# CLK_DISTRO.net
KiCad netlist of a schematic drawn in Altium Designer
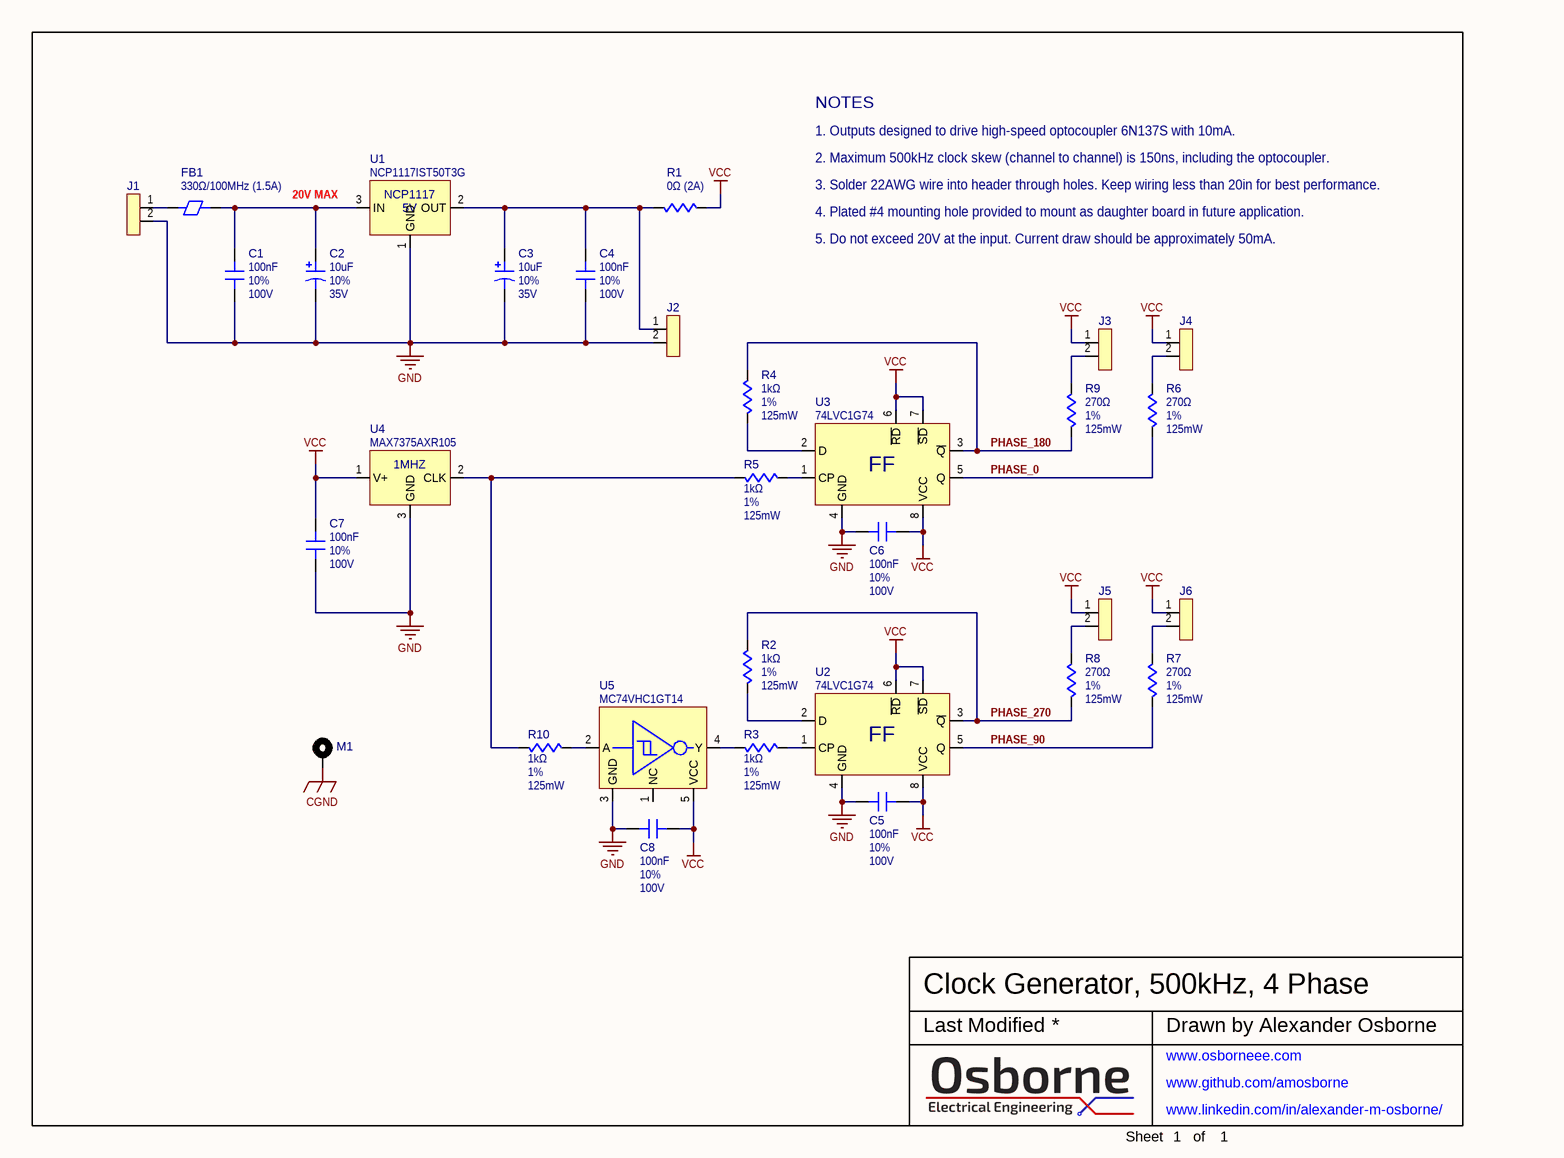
[diagram p0: CLK_DISTRO.SchDoc]

(export (version "E")
  (design (tool "Eeschema 10.0.6"))
  (components
    (comp (ref "C1")
      (value "100nF")
      (footprint "C0805")
      (description "CAP, CER, 100nF ±10%, 100V, 0805")
      (fields
        (field (name "VOLTAGE") "100V")
        (field (name "TOLERANCE") "10%")
        (field (name "Comment") "732-12244-1-ND")
      )
      (libsource (lib "CLK_DISTRO") (part "CAP-CER-100N-10T-100V-0805"))
    )
    (comp (ref "C2")
      (value "10uF")
      (footprint "TRJC")
      (description "CAP, TANT, 10uF ±10%, 35V, 2312")
      (fields
        (field (name "VOLTAGE") "35V")
        (field (name "TOLERANCE") "10%")
        (field (name "Comment") "478-7582-1-ND")
      )
      (libsource (lib "CLK_DISTRO") (part "CAP-TANT-10U-10T-35V-2312"))
    )
    (comp (ref "C3")
      (value "10uF")
      (footprint "TRJC")
      (description "CAP, TANT, 10uF ±10%, 35V, 2312")
      (fields
        (field (name "VOLTAGE") "35V")
        (field (name "TOLERANCE") "10%")
        (field (name "Comment") "478-7582-1-ND")
      )
      (libsource (lib "CLK_DISTRO") (part "CAP-TANT-10U-10T-35V-2312"))
    )
    (comp (ref "C4")
      (value "100nF")
      (footprint "C0805")
      (description "CAP, CER, 100nF ±10%, 100V, 0805")
      (fields
        (field (name "VOLTAGE") "100V")
        (field (name "TOLERANCE") "10%")
        (field (name "Comment") "732-12244-1-ND")
      )
      (libsource (lib "CLK_DISTRO") (part "CAP-CER-100N-10T-100V-0805"))
    )
    (comp (ref "C5")
      (value "100nF")
      (footprint "C0805")
      (description "CAP, CER, 100nF ±10%, 100V, 0805")
      (fields
        (field (name "VOLTAGE") "100V")
        (field (name "TOLERANCE") "10%")
        (field (name "Comment") "732-12244-1-ND")
      )
      (libsource (lib "CLK_DISTRO") (part "CAP-CER-100N-10T-100V-0805"))
    )
    (comp (ref "C6")
      (value "100nF")
      (footprint "C0805")
      (description "CAP, CER, 100nF ±10%, 100V, 0805")
      (fields
        (field (name "VOLTAGE") "100V")
        (field (name "TOLERANCE") "10%")
        (field (name "Comment") "732-12244-1-ND")
      )
      (libsource (lib "CLK_DISTRO") (part "CAP-CER-100N-10T-100V-0805"))
    )
    (comp (ref "C7")
      (value "100nF")
      (footprint "C0805")
      (description "CAP, CER, 100nF ±10%, 100V, 0805")
      (fields
        (field (name "VOLTAGE") "100V")
        (field (name "TOLERANCE") "10%")
        (field (name "Comment") "732-12244-1-ND")
      )
      (libsource (lib "CLK_DISTRO") (part "CAP-CER-100N-10T-100V-0805"))
    )
    (comp (ref "C8")
      (value "100nF")
      (footprint "C0805")
      (description "CAP, CER, 100nF ±10%, 100V, 0805")
      (fields
        (field (name "VOLTAGE") "100V")
        (field (name "TOLERANCE") "10%")
        (field (name "Comment") "732-12244-1-ND")
      )
      (libsource (lib "CLK_DISTRO") (part "CAP-CER-100N-10T-100V-0805"))
    )
    (comp (ref "FB1")
      (value "330Ω/100MHz (1.5A)")
      (footprint "C0805")
      (description "BEAD, 330Ω/100MHz, 1.5A, 0805")
      (fields (field (name "Comment") "553-2394-1-ND"))
      (libsource (lib "CLK_DISTRO") (part "BEAD-330R-1A5-0805"))
    )
    (comp (ref "J1")
      (value "~")
      (footprint "Header_1x2")
      (description "Header 1x2 THT")
      (libsource (lib "") (part "HEADER_1x2_1"))
    )
    (comp (ref "J2")
      (value "~")
      (footprint "Header_1x2")
      (description "Header 1x2 THT")
      (libsource (lib "CLK_DISTRO") (part "HEADER_1x2"))
    )
    (comp (ref "J3")
      (value "~")
      (footprint "Header_1x2")
      (description "Header 1x2 THT")
      (libsource (lib "CLK_DISTRO") (part "HEADER_1x2"))
    )
    (comp (ref "J4")
      (value "~")
      (footprint "Header_1x2")
      (description "Header 1x2 THT")
      (libsource (lib "CLK_DISTRO") (part "HEADER_1x2"))
    )
    (comp (ref "J5")
      (value "~")
      (footprint "Header_1x2")
      (description "Header 1x2 THT")
      (libsource (lib "CLK_DISTRO") (part "HEADER_1x2"))
    )
    (comp (ref "J6")
      (value "~")
      (footprint "Header_1x2")
      (description "Header 1x2 THT")
      (libsource (lib "CLK_DISTRO") (part "HEADER_1x2"))
    )
    (comp (ref "M1")
      (value "~")
      (footprint "MTG_HOLE_No4")
      (description "Mounting Hole")
      (libsource (lib "CLK_DISTRO") (part "MTG_HOLE"))
    )
    (comp (ref "R1")
      (value "0Ω (2A)")
      (footprint "R0805")
      (description "RES, JUMP, 0Ω, 2A, 0805")
      (fields (field (name "Comment") "RMCF0805ZT0R00CT-ND"))
      (libsource (lib "CLK_DISTRO") (part "RES-JUMP-2A-0805"))
    )
    (comp (ref "R2")
      (value "1kΩ")
      (footprint "R0805")
      (description "RES, 1.00kΩ ±1.00%, 125mW, 0805")
      (fields
        (field (name "TOLERANCE") "1%")
        (field (name "POWER") "125mW")
        (field (name "Comment") "RMCF0805FT1K00CT-ND")
      )
      (libsource (lib "CLK_DISTRO") (part "RES-1K00-1T00-W125-0805"))
    )
    (comp (ref "R3")
      (value "1kΩ")
      (footprint "R0805")
      (description "RES, 1.00kΩ ±1.00%, 125mW, 0805")
      (fields
        (field (name "TOLERANCE") "1%")
        (field (name "POWER") "125mW")
        (field (name "Comment") "RMCF0805FT1K00CT-ND")
      )
      (libsource (lib "CLK_DISTRO") (part "RES-1K00-1T00-W125-0805"))
    )
    (comp (ref "R4")
      (value "1kΩ")
      (footprint "R0805")
      (description "RES, 1.00kΩ ±1.00%, 125mW, 0805")
      (fields
        (field (name "TOLERANCE") "1%")
        (field (name "POWER") "125mW")
        (field (name "Comment") "RMCF0805FT1K00CT-ND")
      )
      (libsource (lib "CLK_DISTRO") (part "RES-1K00-1T00-W125-0805"))
    )
    (comp (ref "R5")
      (value "1kΩ")
      (footprint "R0805")
      (description "RES, 1.00kΩ ±1.00%, 125mW, 0805")
      (fields
        (field (name "TOLERANCE") "1%")
        (field (name "POWER") "125mW")
        (field (name "Comment") "RMCF0805FT1K00CT-ND")
      )
      (libsource (lib "CLK_DISTRO") (part "RES-1K00-1T00-W125-0805"))
    )
    (comp (ref "R6")
      (value "270Ω")
      (footprint "R0805")
      (description "RES, 270Ω ±1.00%, 125mW, 0805")
      (fields
        (field (name "TOLERANCE") "1%")
        (field (name "POWER") "125mW")
        (field (name "Comment") "RMCF0805FT270RCT-ND")
      )
      (libsource (lib "CLK_DISTRO") (part "RES-270R-1T00-W125-0805"))
    )
    (comp (ref "R7")
      (value "270Ω")
      (footprint "R0805")
      (description "RES, 270Ω ±1.00%, 125mW, 0805")
      (fields
        (field (name "TOLERANCE") "1%")
        (field (name "POWER") "125mW")
        (field (name "Comment") "RMCF0805FT270RCT-ND")
      )
      (libsource (lib "CLK_DISTRO") (part "RES-270R-1T00-W125-0805"))
    )
    (comp (ref "R8")
      (value "270Ω")
      (footprint "R0805")
      (description "RES, 270Ω ±1.00%, 125mW, 0805")
      (fields
        (field (name "TOLERANCE") "1%")
        (field (name "POWER") "125mW")
        (field (name "Comment") "RMCF0805FT270RCT-ND")
      )
      (libsource (lib "CLK_DISTRO") (part "RES-270R-1T00-W125-0805"))
    )
    (comp (ref "R9")
      (value "270Ω")
      (footprint "R0805")
      (description "RES, 270Ω ±1.00%, 125mW, 0805")
      (fields
        (field (name "TOLERANCE") "1%")
        (field (name "POWER") "125mW")
        (field (name "Comment") "RMCF0805FT270RCT-ND")
      )
      (libsource (lib "CLK_DISTRO") (part "RES-270R-1T00-W125-0805"))
    )
    (comp (ref "R10")
      (value "1kΩ")
      (footprint "R0805")
      (description "RES, 1.00kΩ ±1.00%, 125mW, 0805")
      (fields
        (field (name "TOLERANCE") "1%")
        (field (name "POWER") "125mW")
        (field (name "Comment") "RMCF0805FT1K00CT-ND")
      )
      (libsource (lib "CLK_DISTRO") (part "RES-1K00-1T00-W125-0805"))
    )
    (comp (ref "U1")
      (value "NCP1117IST50T3G")
      (footprint "SOT223")
      (description "Low-Dropout Regulator, 5V, 1A")
      (libsource (lib "CLK_DISTRO") (part "NCP1117IST50T3G"))
    )
    (comp (ref "U2")
      (value "74LVC1G74")
      (footprint "TSSOP-8")
      (description "D-Type Flip-Flop, TTL")
      (libsource (lib "CLK_DISTRO") (part "74LVC1G74"))
    )
    (comp (ref "U3")
      (value "74LVC1G74")
      (footprint "TSSOP-8")
      (description "D-Type Flip-Flop, TTL")
      (libsource (lib "CLK_DISTRO") (part "74LVC1G74"))
    )
    (comp (ref "U4")
      (value "MAX7375AXR105")
      (footprint "SC70")
      (description "OSC, 1MHz, CMOS")
      (libsource (lib "CLK_DISTRO") (part "MAX7375AXR105"))
    )
    (comp (ref "U5")
      (value "MC74VHC1GT14")
      (footprint "TSOP-5")
      (description "Schmitt Trigger Inverter, TTL")
      (libsource (lib "CLK_DISTRO") (part "MC74VHC1GT14"))
    )
  )
  (nets
    (net (code "1") (name "/PHASE_0") (class "Default")
      (node (ref "R6") (pin "2") (pintype "passive"))
      (node (ref "U3") (pin "5") (pinfunction "Q_5") (pintype "passive"))
    )
    (net (code "2") (name "/PHASE_90") (class "Default")
      (node (ref "R7") (pin "2") (pintype "passive"))
      (node (ref "U2") (pin "5") (pinfunction "Q_5") (pintype "passive"))
    )
    (net (code "3") (name "/PHASE_180") (class "Default")
      (node (ref "R4") (pin "2") (pintype "passive"))
      (node (ref "R9") (pin "2") (pintype "passive"))
      (node (ref "U3") (pin "3") (pinfunction "~{Q}_3") (pintype "passive"))
    )
    (net (code "4") (name "/PHASE_270") (class "Default")
      (node (ref "R2") (pin "2") (pintype "passive"))
      (node (ref "R8") (pin "2") (pintype "passive"))
      (node (ref "U2") (pin "3") (pinfunction "~{Q}_3") (pintype "passive"))
    )
    (net (code "5") (name "CGND") (class "Default")
      (node (ref "M1") (pin "1") (pinfunction "12_1") (pintype "passive"))
    )
    (net (code "6") (name "GND") (class "Default")
      (node (ref "C1") (pin "2") (pintype "passive"))
      (node (ref "C2") (pin "2") (pintype "passive"))
      (node (ref "C3") (pin "2") (pintype "passive"))
      (node (ref "C4") (pin "2") (pintype "passive"))
      (node (ref "C5") (pin "2") (pintype "passive"))
      (node (ref "C6") (pin "2") (pintype "passive"))
      (node (ref "C7") (pin "2") (pintype "passive"))
      (node (ref "C8") (pin "2") (pintype "passive"))
      (node (ref "J1") (pin "2") (pinfunction "12_2") (pintype "passive"))
      (node (ref "J2") (pin "2") (pinfunction "12_2") (pintype "passive"))
      (node (ref "U1") (pin "1") (pinfunction "GND_1") (pintype "passive"))
      (node (ref "U2") (pin "4") (pinfunction "GND_4") (pintype "passive"))
      (node (ref "U3") (pin "4") (pinfunction "GND_4") (pintype "passive"))
      (node (ref "U4") (pin "3") (pinfunction "GND_3") (pintype "passive"))
      (node (ref "U5") (pin "3") (pinfunction "GND_3") (pintype "passive"))
    )
    (net (code "7") (name "Net-(FB1-Pad1)") (class "Default")
      (node (ref "FB1") (pin "1") (pintype "passive"))
      (node (ref "J1") (pin "1") (pinfunction "12_1") (pintype "passive"))
    )
    (net (code "8") (name "Net-(J3-12-Pad2)") (class "Default")
      (node (ref "J3") (pin "2") (pinfunction "12_2") (pintype "passive"))
      (node (ref "R9") (pin "1") (pintype "passive"))
    )
    (net (code "9") (name "Net-(J4-12-Pad2)") (class "Default")
      (node (ref "J4") (pin "2") (pinfunction "12_2") (pintype "passive"))
      (node (ref "R6") (pin "1") (pintype "passive"))
    )
    (net (code "10") (name "Net-(J5-12-Pad2)") (class "Default")
      (node (ref "J5") (pin "2") (pinfunction "12_2") (pintype "passive"))
      (node (ref "R8") (pin "1") (pintype "passive"))
    )
    (net (code "11") (name "Net-(J6-12-Pad2)") (class "Default")
      (node (ref "J6") (pin "2") (pinfunction "12_2") (pintype "passive"))
      (node (ref "R7") (pin "1") (pintype "passive"))
    )
    (net (code "12") (name "Net-(U1-IN)") (class "Default")
      (node (ref "C1") (pin "1") (pintype "passive"))
      (node (ref "C2") (pin "1") (pintype "passive"))
      (node (ref "FB1") (pin "2") (pintype "passive"))
      (node (ref "U1") (pin "3") (pinfunction "IN_3") (pintype "passive"))
    )
    (net (code "13") (name "Net-(U1-OUT)") (class "Default")
      (node (ref "C3") (pin "1") (pintype "passive"))
      (node (ref "C4") (pin "1") (pintype "passive"))
      (node (ref "J2") (pin "1") (pinfunction "12_1") (pintype "passive"))
      (node (ref "R1") (pin "1") (pintype "passive"))
      (node (ref "U1") (pin "2") (pinfunction "OUT_2") (pintype "passive"))
    )
    (net (code "14") (name "Net-(U2-CP)") (class "Default")
      (node (ref "R3") (pin "2") (pintype "passive"))
      (node (ref "U2") (pin "1") (pinfunction "CP_1") (pintype "passive"))
    )
    (net (code "15") (name "Net-(U2-D)") (class "Default")
      (node (ref "R2") (pin "1") (pintype "passive"))
      (node (ref "U2") (pin "2") (pinfunction "D_2") (pintype "passive"))
    )
    (net (code "16") (name "Net-(U3-CP)") (class "Default")
      (node (ref "R5") (pin "2") (pintype "passive"))
      (node (ref "U3") (pin "1") (pinfunction "CP_1") (pintype "passive"))
    )
    (net (code "17") (name "Net-(U3-D)") (class "Default")
      (node (ref "R4") (pin "1") (pintype "passive"))
      (node (ref "U3") (pin "2") (pinfunction "D_2") (pintype "passive"))
    )
    (net (code "18") (name "Net-(U4-CLK)") (class "Default")
      (node (ref "R10") (pin "1") (pintype "passive"))
      (node (ref "R5") (pin "1") (pintype "passive"))
      (node (ref "U4") (pin "2") (pinfunction "CLK_2") (pintype "passive"))
    )
    (net (code "19") (name "Net-(U5-A)") (class "Default")
      (node (ref "R10") (pin "2") (pintype "passive"))
      (node (ref "U5") (pin "2") (pinfunction "A_2") (pintype "passive"))
    )
    (net (code "20") (name "Net-(U5-Y)") (class "Default")
      (node (ref "R3") (pin "1") (pintype "passive"))
      (node (ref "U5") (pin "4") (pinfunction "Y_4") (pintype "passive"))
    )
    (net (code "21") (name "VCC") (class "Default")
      (node (ref "C5") (pin "1") (pintype "passive"))
      (node (ref "C6") (pin "1") (pintype "passive"))
      (node (ref "C7") (pin "1") (pintype "passive"))
      (node (ref "C8") (pin "1") (pintype "passive"))
      (node (ref "J3") (pin "1") (pinfunction "12_1") (pintype "passive"))
      (node (ref "J4") (pin "1") (pinfunction "12_1") (pintype "passive"))
      (node (ref "J5") (pin "1") (pinfunction "12_1") (pintype "passive"))
      (node (ref "J6") (pin "1") (pinfunction "12_1") (pintype "passive"))
      (node (ref "R1") (pin "2") (pintype "passive"))
      (node (ref "U2") (pin "6") (pinfunction "~{RD}_6") (pintype "passive"))
      (node (ref "U2") (pin "7") (pinfunction "~{SD}_7") (pintype "passive"))
      (node (ref "U2") (pin "8") (pinfunction "VCC_8") (pintype "passive"))
      (node (ref "U3") (pin "6") (pinfunction "~{RD}_6") (pintype "passive"))
      (node (ref "U3") (pin "7") (pinfunction "~{SD}_7") (pintype "passive"))
      (node (ref "U3") (pin "8") (pinfunction "VCC_8") (pintype "passive"))
      (node (ref "U4") (pin "1") (pinfunction "V+_1") (pintype "passive"))
      (node (ref "U5") (pin "5") (pinfunction "VCC_5") (pintype "passive"))
    )
    (net (code "22") (name "unconnected-(U5-NC-Pad1)") (class "Default")
      (node (ref "U5") (pin "1") (pinfunction "NC_1") (pintype "passive"))
    )
  )
)
